# SENSOR.net
KiCad netlist of a schematic drawn in Altium Designer
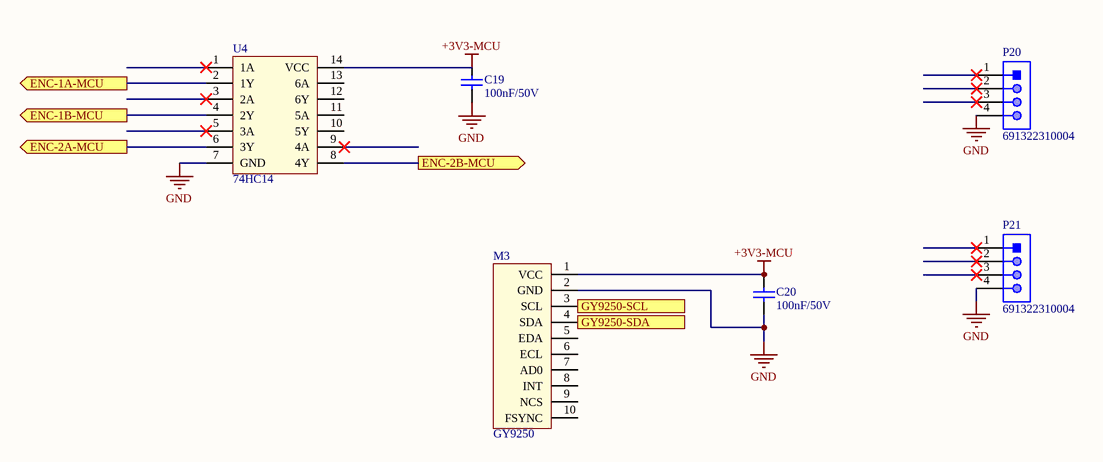
[diagram p0: SENSOR.SchDoc]

(export (version "E")
  (design (tool "Eeschema 10.0.6"))
  (components
    (comp (ref "C19")
      (value "100nF/50V")
      (footprint "CAP-SM-0805")
      (description "CAP CER 0.1UF 50V Y5V 0805")
      (fields
        (field (name "MANUFACTURER") "Samsung Electro-Mechanics")
        (field (name "MANUFACTURER PART NUMBER") "CL21F104ZBCNNNC")
      )
      (libsource (lib "Capacitor") (part "Cap-100nF-50V-0805"))
    )
    (comp (ref "C20")
      (value "100nF/50V")
      (footprint "CAP-SM-0805")
      (description "CAP CER 0.1UF 50V Y5V 0805")
      (fields
        (field (name "MANUFACTURER") "Samsung Electro-Mechanics")
        (field (name "MANUFACTURER PART NUMBER") "CL21F104ZBCNNNC")
      )
      (libsource (lib "Capacitor") (part "Cap-100nF-50V-0805"))
    )
    (comp (ref "M3") (value "GY9250") (footprint "GY9250") (libsource (lib "MyLibrary1") (part "GY9250")))
    (comp (ref "P20")
      (value "691322310004")
      (footprint "691322310004")
      (description "WR-TBL Serie 322 Horizontal PCB Header, Pluggable, pitch 3.81mm, 4p")
      (fields (field (name "PUBLISHER") "Wurth Elektronik"))
      (libsource (lib "691111710003_Altium_WR-TBL_rev19a") (part "691322310004"))
    )
    (comp (ref "P21")
      (value "691322310004")
      (footprint "691322310004")
      (description "WR-TBL Serie 322 Horizontal PCB Header, Pluggable, pitch 3.81mm, 4p")
      (fields (field (name "PUBLISHER") "Wurth Elektronik"))
      (libsource (lib "691111710003_Altium_WR-TBL_rev19a") (part "691322310004"))
    )
    (comp (ref "U4")
      (value "74HC14")
      (footprint "74HC14D,652")
      (libsource (lib "MyLibrary1") (part "74HC14"))
    )
  )
  (nets
    (net (code "1") (name "+3V3-MCU") (class "Default")
      (node (ref "C20") (pin "2") (pinfunction "2_2") (pintype "passive"))
      (node (ref "M3") (pin "1") (pinfunction "VCC_1") (pintype "passive"))
      (node (ref "U4") (pin "14") (pinfunction "VCC_14") (pintype "passive"))
    )
    (net (code "2") (name "/ENC-1A-MCU") (class "Default")
      (node (ref "U4") (pin "2") (pinfunction "1Y_2") (pintype "passive"))
    )
    (net (code "3") (name "/ENC-1B-MCU") (class "Default")
      (node (ref "U4") (pin "4") (pinfunction "2Y_4") (pintype "passive"))
    )
    (net (code "4") (name "/ENC-2A-MCU") (class "Default")
      (node (ref "U4") (pin "6") (pinfunction "3Y_6") (pintype "passive"))
    )
    (net (code "5") (name "/ENC-2B-MCU") (class "Default")
      (node (ref "U4") (pin "8") (pinfunction "4Y_8") (pintype "passive"))
    )
    (net (code "6") (name "/GY9250-SCL") (class "Default")
      (node (ref "M3") (pin "3") (pinfunction "SCL_3") (pintype "passive"))
    )
    (net (code "7") (name "/GY9250-SDA") (class "Default")
      (node (ref "M3") (pin "4") (pinfunction "SDA_4") (pintype "passive"))
    )
    (net (code "8") (name "GND") (class "Default")
      (node (ref "C19") (pin "1") (pinfunction "1_1") (pintype "passive"))
      (node (ref "C20") (pin "1") (pinfunction "1_1") (pintype "passive"))
      (node (ref "M3") (pin "2") (pinfunction "GND_2") (pintype "passive"))
      (node (ref "P20") (pin "4") (pinfunction "4_4") (pintype "passive"))
      (node (ref "P21") (pin "4") (pinfunction "4_4") (pintype "passive"))
      (node (ref "U4") (pin "7") (pinfunction "GND_7") (pintype "passive"))
    )
    (net (code "9") (name "unconnected-(C19-Pad2)") (class "Default")
      (node (ref "C19") (pin "2") (pinfunction "2_2") (pintype "passive"))
    )
    (net (code "10") (name "unconnected-(M3-AD0-Pad7)") (class "Default")
      (node (ref "M3") (pin "7") (pinfunction "AD0_7") (pintype "passive"))
    )
    (net (code "11") (name "unconnected-(M3-ECL-Pad6)") (class "Default")
      (node (ref "M3") (pin "6") (pinfunction "ECL_6") (pintype "passive"))
    )
    (net (code "12") (name "unconnected-(M3-EDA-Pad5)") (class "Default")
      (node (ref "M3") (pin "5") (pinfunction "EDA_5") (pintype "passive"))
    )
    (net (code "13") (name "unconnected-(M3-FSYNC-Pad10)") (class "Default")
      (node (ref "M3") (pin "10") (pinfunction "FSYNC_10") (pintype "passive"))
    )
    (net (code "14") (name "unconnected-(M3-INT-Pad8)") (class "Default")
      (node (ref "M3") (pin "8") (pinfunction "INT_8") (pintype "passive"))
    )
    (net (code "15") (name "unconnected-(M3-NCS-Pad9)") (class "Default")
      (node (ref "M3") (pin "9") (pinfunction "NCS_9") (pintype "passive"))
    )
    (net (code "16") (name "unconnected-(P20-Pad1)") (class "Default")
      (node (ref "P20") (pin "1") (pinfunction "1_1") (pintype "passive+no_connect"))
    )
    (net (code "17") (name "unconnected-(P20-Pad2)") (class "Default")
      (node (ref "P20") (pin "2") (pinfunction "2_2") (pintype "passive+no_connect"))
    )
    (net (code "18") (name "unconnected-(P20-Pad3)") (class "Default")
      (node (ref "P20") (pin "3") (pinfunction "3_3") (pintype "passive+no_connect"))
    )
    (net (code "19") (name "unconnected-(P21-Pad1)") (class "Default")
      (node (ref "P21") (pin "1") (pinfunction "1_1") (pintype "passive+no_connect"))
    )
    (net (code "20") (name "unconnected-(P21-Pad2)") (class "Default")
      (node (ref "P21") (pin "2") (pinfunction "2_2") (pintype "passive+no_connect"))
    )
    (net (code "21") (name "unconnected-(P21-Pad3)") (class "Default")
      (node (ref "P21") (pin "3") (pinfunction "3_3") (pintype "passive+no_connect"))
    )
    (net (code "22") (name "unconnected-(U4-1A-Pad1)") (class "Default")
      (node (ref "U4") (pin "1") (pinfunction "1A_1") (pintype "passive+no_connect"))
    )
    (net (code "23") (name "unconnected-(U4-2A-Pad3)") (class "Default")
      (node (ref "U4") (pin "3") (pinfunction "2A_3") (pintype "passive+no_connect"))
    )
    (net (code "24") (name "unconnected-(U4-3A-Pad5)") (class "Default")
      (node (ref "U4") (pin "5") (pinfunction "3A_5") (pintype "passive+no_connect"))
    )
    (net (code "25") (name "unconnected-(U4-4A-Pad9)") (class "Default")
      (node (ref "U4") (pin "9") (pinfunction "4A_9") (pintype "passive+no_connect"))
    )
    (net (code "26") (name "unconnected-(U4-5A-Pad11)") (class "Default")
      (node (ref "U4") (pin "11") (pinfunction "5A_11") (pintype "passive"))
    )
    (net (code "27") (name "unconnected-(U4-5Y-Pad10)") (class "Default")
      (node (ref "U4") (pin "10") (pinfunction "5Y_10") (pintype "passive"))
    )
    (net (code "28") (name "unconnected-(U4-6A-Pad13)") (class "Default")
      (node (ref "U4") (pin "13") (pinfunction "6A_13") (pintype "passive"))
    )
    (net (code "29") (name "unconnected-(U4-6Y-Pad12)") (class "Default")
      (node (ref "U4") (pin "12") (pinfunction "6Y_12") (pintype "passive"))
    )
  )
)
